# fft.net
KiCad netlist of a schematic drawn in Altium Designer
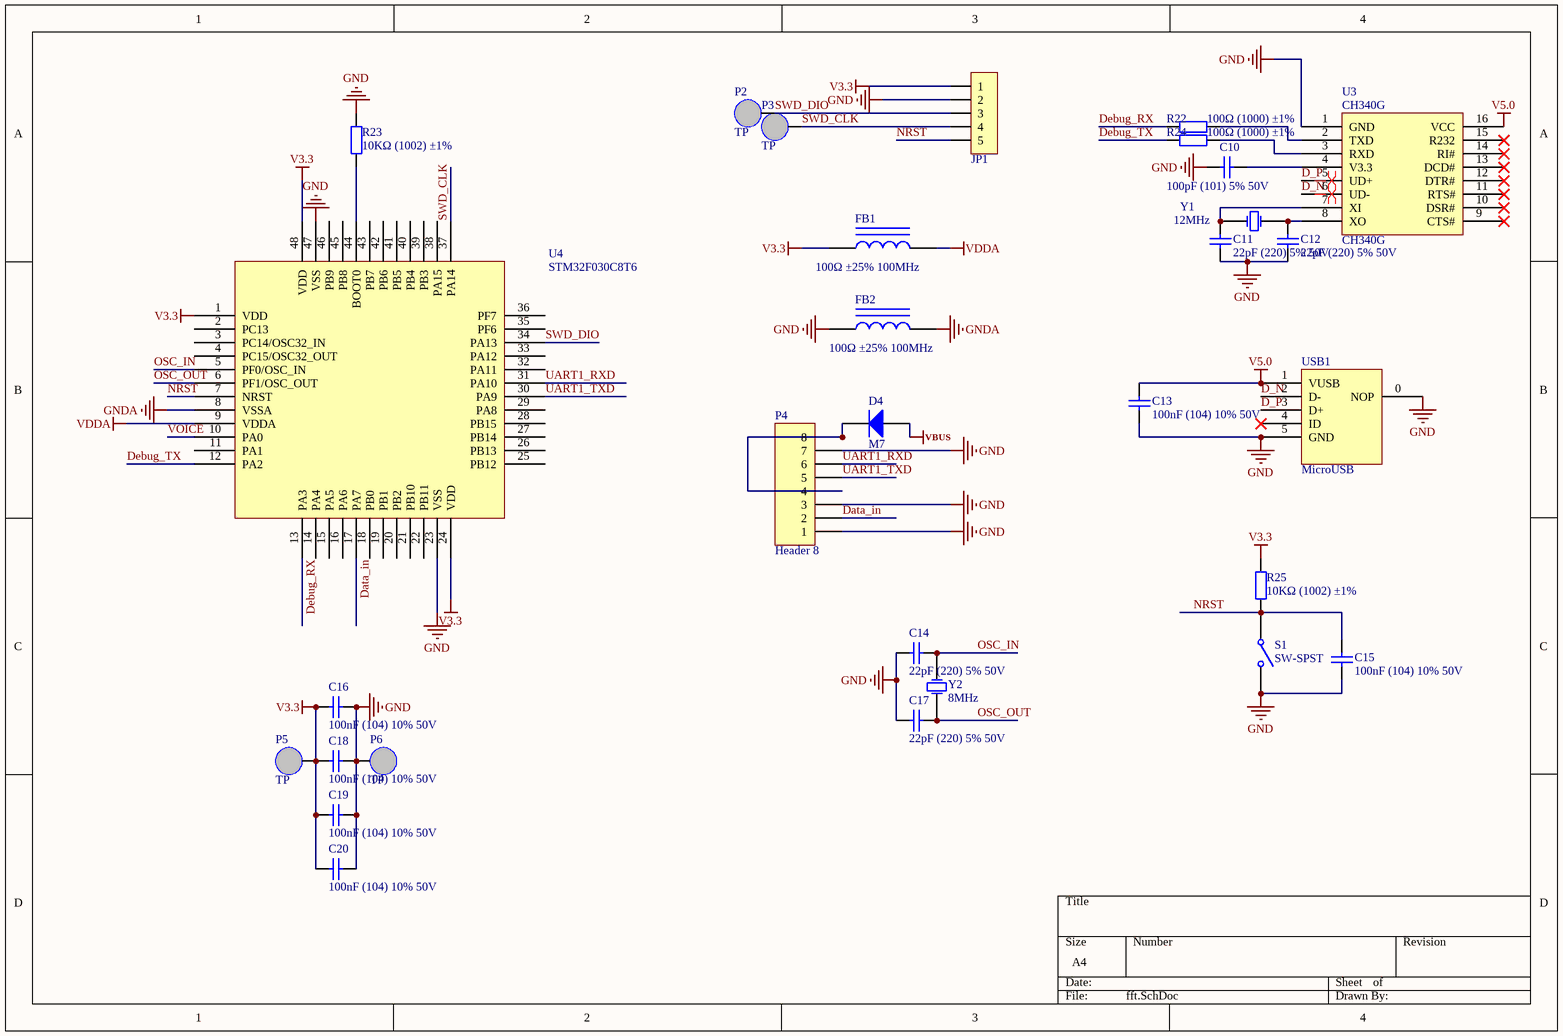
[diagram p0: fft.SchDoc]

(export (version "E")
  (design (tool "Eeschema 10.0.6"))
  (components
    (comp (ref "C10")
      (value "100pF (101) 5% 50V")
      (footprint "0805_C")
      (description "贴片电容")
      (libsource (lib "Miscellaneous Devices LC") (part "0805 100pF (101) 5% 50V"))
    )
    (comp (ref "C11")
      (value "22pF (220) 5% 50V")
      (footprint "0805_C")
      (description "贴片电容")
      (libsource (lib "Miscellaneous Devices LC") (part "0805 22pF (220) 5% 50V"))
    )
    (comp (ref "C12")
      (value "22pF (220) 5% 50V")
      (footprint "0805_C")
      (description "贴片电容")
      (libsource (lib "Miscellaneous Devices LC") (part "0805 22pF (220) 5% 50V"))
    )
    (comp (ref "C13")
      (value "100nF (104) 10% 50V")
      (footprint "0603_C")
      (description "贴片电容")
      (libsource (lib "Miscellaneous Devices LC") (part "0603 100nF (104) 10% 50V"))
    )
    (comp (ref "C14")
      (value "22pF (220) 5% 50V")
      (footprint "0805_C")
      (description "贴片电容")
      (libsource (lib "Miscellaneous Devices LC") (part "0805 22pF (220) 5% 50V"))
    )
    (comp (ref "C15")
      (value "100nF (104) 10% 50V")
      (footprint "0603_C")
      (description "贴片电容")
      (libsource (lib "Miscellaneous Devices LC") (part "0603 100nF (104) 10% 50V"))
    )
    (comp (ref "C16")
      (value "100nF (104) 10% 50V")
      (footprint "0603_C")
      (description "贴片电容")
      (libsource (lib "Miscellaneous Devices LC") (part "0603 100nF (104) 10% 50V"))
    )
    (comp (ref "C17")
      (value "22pF (220) 5% 50V")
      (footprint "0805_C")
      (description "贴片电容")
      (libsource (lib "Miscellaneous Devices LC") (part "0805 22pF (220) 5% 50V"))
    )
    (comp (ref "C18")
      (value "100nF (104) 10% 50V")
      (footprint "0603_C")
      (description "贴片电容")
      (libsource (lib "Miscellaneous Devices LC") (part "0603 100nF (104) 10% 50V"))
    )
    (comp (ref "C19")
      (value "100nF (104) 10% 50V")
      (footprint "0603_C")
      (description "贴片电容")
      (libsource (lib "Miscellaneous Devices LC") (part "0603 100nF (104) 10% 50V"))
    )
    (comp (ref "C20")
      (value "100nF (104) 10% 50V")
      (footprint "0603_C")
      (description "贴片电容")
      (libsource (lib "Miscellaneous Devices LC") (part "0603 100nF (104) 10% 50V"))
    )
    (comp (ref "D4")
      (value "M7")
      (footprint "SMA(DO-214AC)_S1")
      (description "二极管")
      (libsource (lib "Miscellaneous Devices LC") (part "SMA(DO-214AC) M7"))
    )
    (comp (ref "FB1")
      (value "100Ω ±25% 100MHz")
      (footprint "0805_L")
      (description "贴片磁珠")
      (libsource (lib "Miscellaneous Devices LC") (part "0805 100Ω 25% 100MHz"))
    )
    (comp (ref "FB2")
      (value "100Ω ±25% 100MHz")
      (footprint "0805_L")
      (description "贴片磁珠")
      (libsource (lib "Miscellaneous Devices LC") (part "0805 100Ω 25% 100MHz"))
    )
    (comp (ref "JP1")
      (value "HDR-1X5")
      (footprint "XH2.54-LI-5P")
      (description "5P接插件")
      (fields (field (name "版权归属") "源创客"))
      (libsource (lib "4.5   - 接插件-脚距2.54") (part "Header 5"))
    )
    (comp (ref "P2") (value "TP") (footprint "TP") (libsource (lib "mylib") (part "TP")))
    (comp (ref "P3") (value "TP") (footprint "TP") (libsource (lib "mylib") (part "TP")))
    (comp (ref "P4")
      (value "Header 8")
      (footprint "FPC1.0-2H-WS-8P")
      (description "Header, 8-Pin")
      (fields (field (name "PUBLISHER") "Altium Limited"))
      (libsource (lib "Miscellaneous Connectors") (part "Header 8"))
    )
    (comp (ref "P5") (value "TP") (footprint "TP") (libsource (lib "mylib") (part "TP")))
    (comp (ref "P6") (value "TP") (footprint "TP") (libsource (lib "mylib") (part "TP")))
    (comp (ref "R22")
      (value "100Ω (1000) ±1%")
      (footprint "0603_R")
      (description "贴片电阻")
      (libsource (lib "Miscellaneous Devices LC") (part "0603 100Ω (1000) 1%"))
    )
    (comp (ref "R23")
      (value "10KΩ (1002) ±1%")
      (footprint "0603_R")
      (description "贴片电阻")
      (libsource (lib "Miscellaneous Devices LC") (part "0603 10KΩ (1002) 1%"))
    )
    (comp (ref "R24")
      (value "100Ω (1000) ±1%")
      (footprint "0603_R")
      (description "贴片电阻")
      (libsource (lib "Miscellaneous Devices LC") (part "0603 100Ω (1000) 1%"))
    )
    (comp (ref "R25")
      (value "10KΩ (1002) ±1%")
      (footprint "0805_R")
      (description "贴片电阻")
      (libsource (lib "Miscellaneous Devices LC") (part "0805 10KΩ (1002) 1%"))
    )
    (comp (ref "S1")
      (value "SW-SPST")
      (footprint "TSW SMD-3*6*2.5")
      (description "Single-Pole, Single-Throw Switch")
      (fields (field (name "PUBLISHER") "Altium Limited"))
      (libsource (lib "Miscellaneous Devices") (part "SW-SPST"))
    )
    (comp (ref "U3")
      (value "CH340G")
      (footprint "SOIC-16_150mil")
      (description "USB")
      (libsource (lib "Miscellaneous Devices LC") (part "CH340G_[C14267]"))
    )
    (comp (ref "U4")
      (value "STM32F030C8T6")
      (footprint "LQFP-48_7x7x05P")
      (description "ARM")
      (libsource (lib "Miscellaneous Devices LC") (part "STM32F030C8T6"))
    )
    (comp (ref "USB1") (value "MicroUSB") (footprint "MicroUSB") (libsource (lib "mylib") (part "MicroUSB")))
    (comp (ref "Y1")
      (value "12MHz")
      (footprint "Y")
      (description "贴片晶振")
      (libsource (lib "Miscellaneous Devices LC") (part "SMD-5032_2P 8MHz 20ppm 20pF"))
    )
    (comp (ref "Y2")
      (value "8MHz")
      (footprint "SMD-5032_2P")
      (description "贴片晶振")
      (libsource (lib "Miscellaneous Devices LC") (part "SMD-5032_2P 8MHz 20ppm 20pF"))
    )
  )
  (nets
    (net (code "1") (name "/D_N") (class "Default")
      (node (ref "U3") (pin "6") (pinfunction "UD-_6") (pintype "passive"))
      (node (ref "USB1") (pin "2") (pinfunction "D-_2") (pintype "passive"))
    )
    (net (code "2") (name "/D_P") (class "Default")
      (node (ref "U3") (pin "5") (pinfunction "UD+_5") (pintype "passive"))
      (node (ref "USB1") (pin "3") (pinfunction "D+_3") (pintype "passive"))
    )
    (net (code "3") (name "/Data_in") (class "Default")
      (node (ref "P4") (pin "2") (pinfunction "2_2") (pintype "passive"))
      (node (ref "U4") (pin "17") (pinfunction "PA7_17") (pintype "passive"))
    )
    (net (code "4") (name "/Debug_RX") (class "Default")
      (node (ref "R22") (pin "1") (pinfunction "1_1") (pintype "passive"))
      (node (ref "U4") (pin "13") (pinfunction "PA3_13") (pintype "passive"))
    )
    (net (code "5") (name "/Debug_TX") (class "Default")
      (node (ref "R24") (pin "1") (pinfunction "1_1") (pintype "passive"))
      (node (ref "U4") (pin "12") (pinfunction "PA2_12") (pintype "passive"))
    )
    (net (code "6") (name "/NRST") (class "Default")
      (node (ref "C15") (pin "2") (pinfunction "2_2") (pintype "passive"))
      (node (ref "JP1") (pin "5") (pinfunction "5_5") (pintype "passive"))
      (node (ref "R25") (pin "1") (pinfunction "1_1") (pintype "passive"))
      (node (ref "S1") (pin "1") (pinfunction "COMMON_1") (pintype "passive"))
      (node (ref "U4") (pin "7") (pinfunction "NRST_7") (pintype "passive"))
    )
    (net (code "7") (name "/OSC_IN") (class "Default")
      (node (ref "C14") (pin "1") (pinfunction "1_1") (pintype "passive"))
      (node (ref "U4") (pin "5") (pinfunction "PF0/OSC_IN_5") (pintype "passive"))
      (node (ref "Y2") (pin "1") (pinfunction "OSC1_1") (pintype "passive"))
    )
    (net (code "8") (name "/OSC_OUT") (class "Default")
      (node (ref "C17") (pin "1") (pinfunction "1_1") (pintype "passive"))
      (node (ref "U4") (pin "6") (pinfunction "PF1/OSC_OUT_6") (pintype "passive"))
      (node (ref "Y2") (pin "2") (pinfunction "OSC2_2") (pintype "passive"))
    )
    (net (code "9") (name "/SWD_CLK") (class "Default")
      (node (ref "JP1") (pin "4") (pinfunction "4_4") (pintype "passive"))
      (node (ref "P3") (pin "1") (pinfunction "1_1") (pintype "passive"))
      (node (ref "U4") (pin "37") (pinfunction "PA14_37") (pintype "passive"))
    )
    (net (code "10") (name "/SWD_DIO") (class "Default")
      (node (ref "JP1") (pin "3") (pinfunction "3_3") (pintype "passive"))
      (node (ref "P2") (pin "1") (pinfunction "1_1") (pintype "passive"))
      (node (ref "U4") (pin "34") (pinfunction "PA13_34") (pintype "passive"))
    )
    (net (code "11") (name "/UART1_RXD") (class "Default")
      (node (ref "P4") (pin "6") (pinfunction "6_6") (pintype "passive"))
      (node (ref "U4") (pin "31") (pinfunction "PA10_31") (pintype "passive"))
    )
    (net (code "12") (name "/UART1_TXD") (class "Default")
      (node (ref "P4") (pin "5") (pinfunction "5_5") (pintype "passive"))
      (node (ref "U4") (pin "30") (pinfunction "PA9_30") (pintype "passive"))
    )
    (net (code "13") (name "/VOICE") (class "Default")
      (node (ref "U4") (pin "10") (pinfunction "PA0_10") (pintype "passive"))
    )
    (net (code "14") (name "GND") (class "Default")
      (node (ref "C10") (pin "1") (pinfunction "1_1") (pintype "passive"))
      (node (ref "C11") (pin "2") (pinfunction "2_2") (pintype "passive"))
      (node (ref "C12") (pin "2") (pinfunction "2_2") (pintype "passive"))
      (node (ref "C13") (pin "1") (pinfunction "1_1") (pintype "passive"))
      (node (ref "C14") (pin "2") (pinfunction "2_2") (pintype "passive"))
      (node (ref "C15") (pin "1") (pinfunction "1_1") (pintype "passive"))
      (node (ref "C16") (pin "2") (pinfunction "2_2") (pintype "passive"))
      (node (ref "C17") (pin "2") (pinfunction "2_2") (pintype "passive"))
      (node (ref "C18") (pin "2") (pinfunction "2_2") (pintype "passive"))
      (node (ref "C19") (pin "2") (pinfunction "2_2") (pintype "passive"))
      (node (ref "C20") (pin "2") (pinfunction "2_2") (pintype "passive"))
      (node (ref "FB2") (pin "1") (pinfunction "1_1") (pintype "passive"))
      (node (ref "JP1") (pin "2") (pinfunction "2_2") (pintype "passive"))
      (node (ref "P4") (pin "1") (pinfunction "1_1") (pintype "passive"))
      (node (ref "P4") (pin "3") (pinfunction "3_3") (pintype "passive"))
      (node (ref "P4") (pin "7") (pinfunction "7_7") (pintype "passive"))
      (node (ref "P6") (pin "1") (pinfunction "1_1") (pintype "passive"))
      (node (ref "R23") (pin "2") (pinfunction "2_2") (pintype "passive"))
      (node (ref "S1") (pin "2") (pinfunction "NO_2") (pintype "passive"))
      (node (ref "U3") (pin "1") (pinfunction "GND_1") (pintype "passive"))
      (node (ref "U4") (pin "23") (pinfunction "VSS_23") (pintype "passive"))
      (node (ref "U4") (pin "47") (pinfunction "VSS_47") (pintype "passive"))
      (node (ref "USB1") (pin "0") (pinfunction "NOP_0") (pintype "passive"))
      (node (ref "USB1") (pin "5") (pinfunction "GND_5") (pintype "passive"))
    )
    (net (code "15") (name "GNDA") (class "Default")
      (node (ref "FB2") (pin "2") (pinfunction "2_2") (pintype "passive"))
      (node (ref "U4") (pin "8") (pinfunction "VSSA_8") (pintype "passive"))
    )
    (net (code "16") (name "Net-(D4-K)") (class "Default")
      (node (ref "D4") (pin "2") (pinfunction "K_2") (pintype "passive"))
      (node (ref "P4") (pin "4") (pinfunction "4_4") (pintype "passive"))
      (node (ref "P4") (pin "8") (pinfunction "8_8") (pintype "passive"))
    )
    (net (code "17") (name "Net-(U3-RXD)") (class "Default")
      (node (ref "R24") (pin "2") (pinfunction "2_2") (pintype "passive"))
      (node (ref "U3") (pin "3") (pinfunction "RXD_3") (pintype "passive"))
    )
    (net (code "18") (name "Net-(U3-TXD)") (class "Default")
      (node (ref "R22") (pin "2") (pinfunction "2_2") (pintype "passive"))
      (node (ref "U3") (pin "2") (pinfunction "TXD_2") (pintype "passive"))
    )
    (net (code "19") (name "Net-(U3-V3.3)") (class "Default")
      (node (ref "C10") (pin "2") (pinfunction "2_2") (pintype "passive"))
      (node (ref "U3") (pin "4") (pinfunction "V3.3_4") (pintype "passive"))
    )
    (net (code "20") (name "Net-(U3-XI)") (class "Default")
      (node (ref "C11") (pin "1") (pinfunction "1_1") (pintype "passive"))
      (node (ref "U3") (pin "7") (pinfunction "XI_7") (pintype "passive"))
      (node (ref "Y1") (pin "1") (pinfunction "OSC1_1") (pintype "passive"))
    )
    (net (code "21") (name "Net-(U3-XO)") (class "Default")
      (node (ref "C12") (pin "1") (pinfunction "1_1") (pintype "passive"))
      (node (ref "U3") (pin "8") (pinfunction "XO_8") (pintype "passive"))
      (node (ref "Y1") (pin "2") (pinfunction "OSC2_2") (pintype "passive"))
    )
    (net (code "22") (name "Net-(U4-BOOT0)") (class "Default")
      (node (ref "R23") (pin "1") (pinfunction "1_1") (pintype "passive"))
      (node (ref "U4") (pin "44") (pinfunction "BOOT0_44") (pintype "passive"))
    )
    (net (code "23") (name "V3.3") (class "Default")
      (node (ref "C16") (pin "1") (pinfunction "1_1") (pintype "passive"))
      (node (ref "C18") (pin "1") (pinfunction "1_1") (pintype "passive"))
      (node (ref "C19") (pin "1") (pinfunction "1_1") (pintype "passive"))
      (node (ref "C20") (pin "1") (pinfunction "1_1") (pintype "passive"))
      (node (ref "FB1") (pin "1") (pinfunction "1_1") (pintype "passive"))
      (node (ref "JP1") (pin "1") (pinfunction "1_1") (pintype "passive"))
      (node (ref "P5") (pin "1") (pinfunction "1_1") (pintype "passive"))
      (node (ref "R25") (pin "2") (pinfunction "2_2") (pintype "passive"))
      (node (ref "U4") (pin "1") (pinfunction "VDD_1") (pintype "passive"))
      (node (ref "U4") (pin "24") (pinfunction "VDD_24") (pintype "passive"))
      (node (ref "U4") (pin "48") (pinfunction "VDD_48") (pintype "passive"))
    )
    (net (code "24") (name "V5.0") (class "Default")
      (node (ref "C13") (pin "2") (pinfunction "2_2") (pintype "passive"))
      (node (ref "U3") (pin "16") (pinfunction "VCC_16") (pintype "passive"))
      (node (ref "USB1") (pin "1") (pinfunction "VUSB_1") (pintype "passive"))
    )
    (net (code "25") (name "VBUS") (class "Default")
      (node (ref "D4") (pin "1") (pinfunction "A_1") (pintype "passive"))
    )
    (net (code "26") (name "VDDA") (class "Default")
      (node (ref "FB1") (pin "2") (pinfunction "2_2") (pintype "passive"))
      (node (ref "U4") (pin "9") (pinfunction "VDDA_9") (pintype "passive"))
    )
    (net (code "27") (name "unconnected-(U3-CTS#-Pad9)") (class "Default")
      (node (ref "U3") (pin "9") (pinfunction "CTS#_9") (pintype "passive+no_connect"))
    )
    (net (code "28") (name "unconnected-(U3-DCD#-Pad13)") (class "Default")
      (node (ref "U3") (pin "13") (pinfunction "DCD#_13") (pintype "passive+no_connect"))
    )
    (net (code "29") (name "unconnected-(U3-DSR#-Pad10)") (class "Default")
      (node (ref "U3") (pin "10") (pinfunction "DSR#_10") (pintype "passive+no_connect"))
    )
    (net (code "30") (name "unconnected-(U3-DTR#-Pad12)") (class "Default")
      (node (ref "U3") (pin "12") (pinfunction "DTR#_12") (pintype "passive+no_connect"))
    )
    (net (code "31") (name "unconnected-(U3-R232-Pad15)") (class "Default")
      (node (ref "U3") (pin "15") (pinfunction "R232_15") (pintype "passive+no_connect"))
    )
    (net (code "32") (name "unconnected-(U3-RI#-Pad14)") (class "Default")
      (node (ref "U3") (pin "14") (pinfunction "RI#_14") (pintype "passive+no_connect"))
    )
    (net (code "33") (name "unconnected-(U3-RTS#-Pad11)") (class "Default")
      (node (ref "U3") (pin "11") (pinfunction "RTS#_11") (pintype "passive+no_connect"))
    )
    (net (code "34") (name "unconnected-(U4-PA1-Pad11)") (class "Default")
      (node (ref "U4") (pin "11") (pinfunction "PA1_11") (pintype "passive"))
    )
    (net (code "35") (name "unconnected-(U4-PA4-Pad14)") (class "Default")
      (node (ref "U4") (pin "14") (pinfunction "PA4_14") (pintype "passive"))
    )
    (net (code "36") (name "unconnected-(U4-PA5-Pad15)") (class "Default")
      (node (ref "U4") (pin "15") (pinfunction "PA5_15") (pintype "passive"))
    )
    (net (code "37") (name "unconnected-(U4-PA6-Pad16)") (class "Default")
      (node (ref "U4") (pin "16") (pinfunction "PA6_16") (pintype "passive"))
    )
    (net (code "38") (name "unconnected-(U4-PA8-Pad29)") (class "Default")
      (node (ref "U4") (pin "29") (pinfunction "PA8_29") (pintype "passive"))
    )
    (net (code "39") (name "unconnected-(U4-PA11-Pad32)") (class "Default")
      (node (ref "U4") (pin "32") (pinfunction "PA11_32") (pintype "passive"))
    )
    (net (code "40") (name "unconnected-(U4-PA12-Pad33)") (class "Default")
      (node (ref "U4") (pin "33") (pinfunction "PA12_33") (pintype "passive"))
    )
    (net (code "41") (name "unconnected-(U4-PA15-Pad38)") (class "Default")
      (node (ref "U4") (pin "38") (pinfunction "PA15_38") (pintype "passive"))
    )
    (net (code "42") (name "unconnected-(U4-PB0-Pad18)") (class "Default")
      (node (ref "U4") (pin "18") (pinfunction "PB0_18") (pintype "passive"))
    )
    (net (code "43") (name "unconnected-(U4-PB1-Pad19)") (class "Default")
      (node (ref "U4") (pin "19") (pinfunction "PB1_19") (pintype "passive"))
    )
    (net (code "44") (name "unconnected-(U4-PB2-Pad20)") (class "Default")
      (node (ref "U4") (pin "20") (pinfunction "PB2_20") (pintype "passive"))
    )
    (net (code "45") (name "unconnected-(U4-PB3-Pad39)") (class "Default")
      (node (ref "U4") (pin "39") (pinfunction "PB3_39") (pintype "passive"))
    )
    (net (code "46") (name "unconnected-(U4-PB4-Pad40)") (class "Default")
      (node (ref "U4") (pin "40") (pinfunction "PB4_40") (pintype "passive"))
    )
    (net (code "47") (name "unconnected-(U4-PB5-Pad41)") (class "Default")
      (node (ref "U4") (pin "41") (pinfunction "PB5_41") (pintype "passive"))
    )
    (net (code "48") (name "unconnected-(U4-PB6-Pad42)") (class "Default")
      (node (ref "U4") (pin "42") (pinfunction "PB6_42") (pintype "passive"))
    )
    (net (code "49") (name "unconnected-(U4-PB7-Pad43)") (class "Default")
      (node (ref "U4") (pin "43") (pinfunction "PB7_43") (pintype "passive"))
    )
    (net (code "50") (name "unconnected-(U4-PB8-Pad45)") (class "Default")
      (node (ref "U4") (pin "45") (pinfunction "PB8_45") (pintype "passive"))
    )
    (net (code "51") (name "unconnected-(U4-PB9-Pad46)") (class "Default")
      (node (ref "U4") (pin "46") (pinfunction "PB9_46") (pintype "passive"))
    )
    (net (code "52") (name "unconnected-(U4-PB10-Pad21)") (class "Default")
      (node (ref "U4") (pin "21") (pinfunction "PB10_21") (pintype "passive"))
    )
    (net (code "53") (name "unconnected-(U4-PB11-Pad22)") (class "Default")
      (node (ref "U4") (pin "22") (pinfunction "PB11_22") (pintype "passive"))
    )
    (net (code "54") (name "unconnected-(U4-PB12-Pad25)") (class "Default")
      (node (ref "U4") (pin "25") (pinfunction "PB12_25") (pintype "passive"))
    )
    (net (code "55") (name "unconnected-(U4-PB13-Pad26)") (class "Default")
      (node (ref "U4") (pin "26") (pinfunction "PB13_26") (pintype "passive"))
    )
    (net (code "56") (name "unconnected-(U4-PB14-Pad27)") (class "Default")
      (node (ref "U4") (pin "27") (pinfunction "PB14_27") (pintype "passive"))
    )
    (net (code "57") (name "unconnected-(U4-PB15-Pad28)") (class "Default")
      (node (ref "U4") (pin "28") (pinfunction "PB15_28") (pintype "passive"))
    )
    (net (code "58") (name "unconnected-(U4-PC13-Pad2)") (class "Default")
      (node (ref "U4") (pin "2") (pinfunction "PC13_2") (pintype "passive"))
    )
    (net (code "59") (name "unconnected-(U4-PC14{slash}OSC32_IN-Pad3)") (class "Default")
      (node (ref "U4") (pin "3") (pinfunction "PC14/OSC32_IN_3") (pintype "passive"))
    )
    (net (code "60") (name "unconnected-(U4-PC15{slash}OSC32_OUT-Pad4)") (class "Default")
      (node (ref "U4") (pin "4") (pinfunction "PC15/OSC32_OUT_4") (pintype "passive"))
    )
    (net (code "61") (name "unconnected-(U4-PF6-Pad35)") (class "Default")
      (node (ref "U4") (pin "35") (pinfunction "PF6_35") (pintype "passive"))
    )
    (net (code "62") (name "unconnected-(U4-PF7-Pad36)") (class "Default")
      (node (ref "U4") (pin "36") (pinfunction "PF7_36") (pintype "passive"))
    )
    (net (code "63") (name "unconnected-(USB1-ID-Pad4)") (class "Default")
      (node (ref "USB1") (pin "4") (pinfunction "ID_4") (pintype "passive+no_connect"))
    )
  )
)
